# Final.net
KiCad netlist of a schematic drawn in EasyEDA
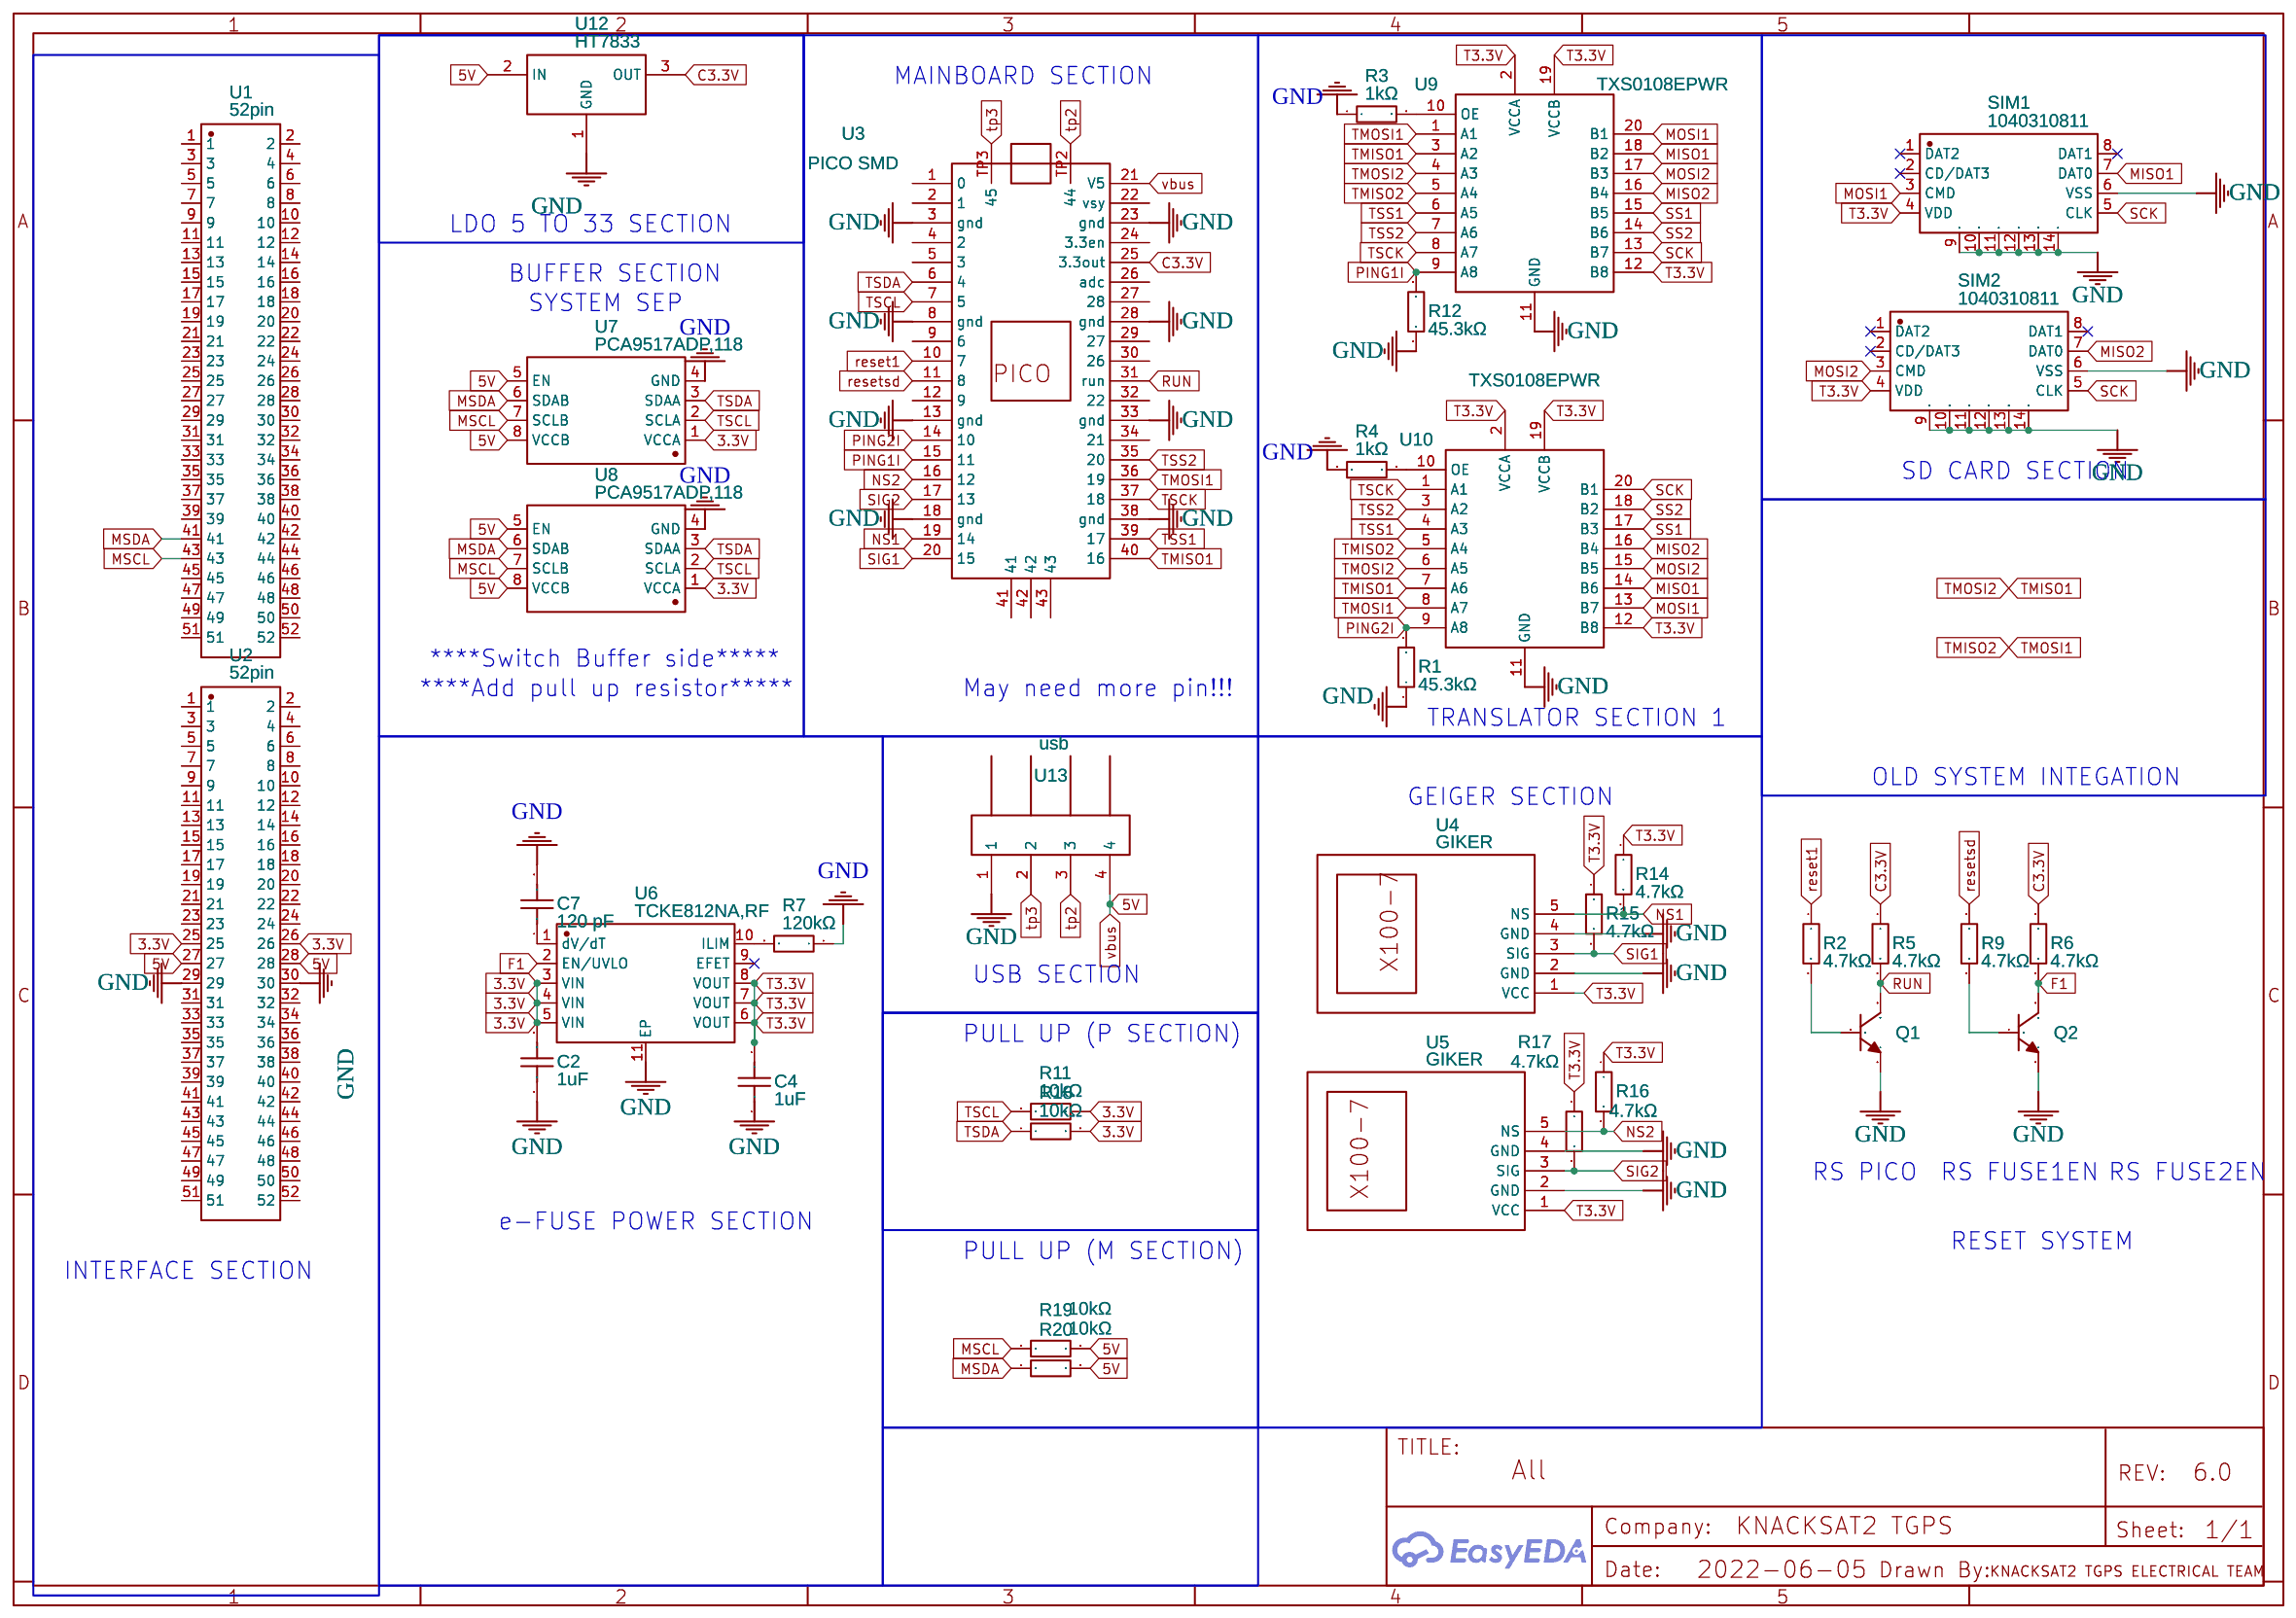
[diagram p0: schematic sheet]

(export (version "E")
  (design (tool "Eeschema 10.0.6"))
  (components
    (comp (ref "C2") (value "1uF") (libsource (lib "") (part "C_0603_US")))
    (comp (ref "C4") (value "1uF") (libsource (lib "") (part "C_0603_US")))
    (comp (ref "C7") (value "120 pF") (libsource (lib "") (part "C_0603_US")))
    (comp (ref "Q1")
      (value "2SC3324-BL(TE85L,F")
      (fields (field (name "BOM_Supplier Part") "C2999171"))
      (libsource (lib "") (part "2SC3324-BL(TE85L,F"))
    )
    (comp (ref "Q2")
      (value "2SC3324-BL(TE85L,F")
      (fields (field (name "BOM_Supplier Part") "C2999171"))
      (libsource (lib "") (part "2SC3324-BL(TE85L,F"))
    )
    (comp (ref "R1")
      (value "45.3kΩ")
      (fields
        (field (name "BOM_Manufacturer Part") "RMC040245.3K1%N")
        (field (name "BOM_Supplier Part") "C325554")
      )
      (libsource (lib "") (part "RMC040245.3K1%N"))
    )
    (comp (ref "R2")
      (value "4.7kΩ")
      (fields
        (field (name "BOM_Manufacturer Part") "RMC08054.7K1%N")
        (field (name "BOM_Supplier Part") "C269746")
      )
      (libsource (lib "") (part "RMC08054.7K1%N"))
    )
    (comp (ref "R3")
      (value "1kΩ")
      (fields
        (field (name "BOM_Manufacturer Part") "PTFR0805B1K00N9")
        (field (name "BOM_Supplier Part") "C328437")
      )
      (libsource (lib "") (part "PTFR0805B1K00N9"))
    )
    (comp (ref "R4")
      (value "1kΩ")
      (fields
        (field (name "BOM_Manufacturer Part") "PTFR0805B1K00N9")
        (field (name "BOM_Supplier Part") "C328437")
      )
      (libsource (lib "") (part "PTFR0805B1K00N9"))
    )
    (comp (ref "R5")
      (value "4.7kΩ")
      (fields
        (field (name "BOM_Manufacturer Part") "RMC08054.7K1%N")
        (field (name "BOM_Supplier Part") "C269746")
      )
      (libsource (lib "") (part "RMC08054.7K1%N"))
    )
    (comp (ref "R6")
      (value "4.7kΩ")
      (fields
        (field (name "BOM_Manufacturer Part") "RMC08054.7K1%N")
        (field (name "BOM_Supplier Part") "C269746")
      )
      (libsource (lib "") (part "RMC08054.7K1%N"))
    )
    (comp (ref "R7")
      (value "120kΩ")
      (fields
        (field (name "BOM_Manufacturer Part") "RMC0402120K1%N")
        (field (name "BOM_Supplier Part") "C325558")
      )
      (libsource (lib "") (part "RMC0402120K1%N"))
    )
    (comp (ref "R9")
      (value "4.7kΩ")
      (fields
        (field (name "BOM_Manufacturer Part") "RMC08054.7K1%N")
        (field (name "BOM_Supplier Part") "C269746")
      )
      (libsource (lib "") (part "RMC08054.7K1%N"))
    )
    (comp (ref "R11")
      (value "10kΩ")
      (fields
        (field (name "BOM_Manufacturer Part") "AECR0805F10K0K9")
        (field (name "BOM_Supplier Part") "C328381")
      )
      (libsource (lib "") (part "AECR0805F10K0K9"))
    )
    (comp (ref "R12")
      (value "45.3kΩ")
      (fields
        (field (name "BOM_Manufacturer Part") "RMC040245.3K1%N")
        (field (name "BOM_Supplier Part") "C325554")
      )
      (libsource (lib "") (part "RMC040245.3K1%N"))
    )
    (comp (ref "R14")
      (value "4.7kΩ")
      (fields
        (field (name "BOM_Manufacturer Part") "RMC08054.7K1%N")
        (field (name "BOM_Supplier Part") "C269746")
      )
      (libsource (lib "") (part "RMC08054.7K1%N"))
    )
    (comp (ref "R15")
      (value "4.7kΩ")
      (fields
        (field (name "BOM_Manufacturer Part") "RMC08054.7K1%N")
        (field (name "BOM_Supplier Part") "C269746")
      )
      (libsource (lib "") (part "RMC08054.7K1%N"))
    )
    (comp (ref "R16")
      (value "4.7kΩ")
      (fields
        (field (name "BOM_Manufacturer Part") "RMC08054.7K1%N")
        (field (name "BOM_Supplier Part") "C269746")
      )
      (libsource (lib "") (part "RMC08054.7K1%N"))
    )
    (comp (ref "R17")
      (value "4.7kΩ")
      (fields
        (field (name "BOM_Manufacturer Part") "RMC08054.7K1%N")
        (field (name "BOM_Supplier Part") "C269746")
      )
      (libsource (lib "") (part "RMC08054.7K1%N"))
    )
    (comp (ref "R18")
      (value "10kΩ")
      (fields
        (field (name "BOM_Manufacturer Part") "AECR0805F10K0K9")
        (field (name "BOM_Supplier Part") "C328381")
      )
      (libsource (lib "") (part "AECR0805F10K0K9"))
    )
    (comp (ref "R19")
      (value "10kΩ")
      (fields
        (field (name "BOM_Manufacturer Part") "AECR0805F10K0K9")
        (field (name "BOM_Supplier Part") "C328381")
      )
      (libsource (lib "") (part "AECR0805F10K0K9"))
    )
    (comp (ref "R20")
      (value "10kΩ")
      (fields
        (field (name "BOM_Manufacturer Part") "AECR0805F10K0K9")
        (field (name "BOM_Supplier Part") "C328381")
      )
      (libsource (lib "") (part "AECR0805F10K0K9"))
    )
    (comp (ref "SIM1")
      (value "1040310811")
      (fields (field (name "BOM_Supplier Part") "C585350"))
      (libsource (lib "") (part "1040310811"))
    )
    (comp (ref "SIM2")
      (value "1040310811")
      (fields (field (name "BOM_Supplier Part") "C585350"))
      (libsource (lib "") (part "1040310811"))
    )
    (comp (ref "U1") (value "52pin") (libsource (lib "") (part "52pin")))
    (comp (ref "U2") (value "52pin") (libsource (lib "") (part "52pin")))
    (comp (ref "U3") (value "PICO SMD") (libsource (lib "") (part "PICO SMD")))
    (comp (ref "U4") (value "GIKER") (libsource (lib "") (part "GIKER")))
    (comp (ref "U5") (value "GIKER") (libsource (lib "") (part "GIKER_1")))
    (comp (ref "U6")
      (value "TCKE812NA,RF")
      (fields (field (name "BOM_Supplier Part") "C1880271"))
      (libsource (lib "") (part "TCKE812NA,RF"))
    )
    (comp (ref "U7")
      (value "PCA9517ADP,118")
      (fields (field (name "BOM_Supplier Part") "C80799"))
      (libsource (lib "") (part "PCA9517ADP,118"))
    )
    (comp (ref "U8")
      (value "PCA9517ADP,118")
      (fields (field (name "BOM_Supplier Part") "C80799"))
      (libsource (lib "") (part "PCA9517ADP,118"))
    )
    (comp (ref "U9")
      (value "TXS0108EPWR")
      (fields (field (name "BOM_Supplier Part") "C17206"))
      (libsource (lib "") (part "TXS0108EPWR"))
    )
    (comp (ref "U10")
      (value "TXS0108EPWR")
      (fields (field (name "BOM_Supplier Part") "C17206"))
      (libsource (lib "") (part "TXS0108EPWR"))
    )
    (comp (ref "U12")
      (value "HT7833")
      (fields (field (name "BOM_Supplier Part") "C50936"))
      (libsource (lib "") (part "HT7833"))
    )
    (comp (ref "U13") (value "usb") (libsource (lib "") (part "usb")))
  )
  (nets
    (net (code "1") (name "3.3V") (class "Default")
      (node (ref "C2") (pin "2") (pinfunction "2_2") (pintype "unspecified"))
      (node (ref "R11") (pin "2") (pinfunction "2_2") (pintype "unspecified"))
      (node (ref "R18") (pin "2") (pinfunction "2_2") (pintype "unspecified"))
      (node (ref "U2") (pin "25") (pinfunction "25_25") (pintype "unspecified"))
      (node (ref "U2") (pin "26") (pinfunction "26_26") (pintype "unspecified"))
      (node (ref "U6") (pin "3") (pinfunction "VIN_3") (pintype "unspecified"))
      (node (ref "U6") (pin "4") (pinfunction "VIN_4") (pintype "unspecified"))
      (node (ref "U6") (pin "5") (pinfunction "VIN_5") (pintype "unspecified"))
      (node (ref "U7") (pin "1") (pinfunction "VCCA_1") (pintype "unspecified"))
      (node (ref "U8") (pin "1") (pinfunction "VCCA_1") (pintype "unspecified"))
    )
    (net (code "2") (name "5V") (class "Default")
      (node (ref "R19") (pin "2") (pinfunction "2_2") (pintype "unspecified"))
      (node (ref "R20") (pin "2") (pinfunction "2_2") (pintype "unspecified"))
      (node (ref "U12") (pin "2") (pinfunction "IN_2") (pintype "passive"))
      (node (ref "U13") (pin "4") (pinfunction "4_4") (pintype "unspecified"))
      (node (ref "U2") (pin "27") (pinfunction "27_27") (pintype "unspecified"))
      (node (ref "U2") (pin "28") (pinfunction "28_28") (pintype "unspecified"))
      (node (ref "U3") (pin "21") (pinfunction "V5_21") (pintype "unspecified"))
      (node (ref "U7") (pin "5") (pinfunction "EN_5") (pintype "unspecified"))
      (node (ref "U7") (pin "8") (pinfunction "VCCB_8") (pintype "unspecified"))
      (node (ref "U8") (pin "5") (pinfunction "EN_5") (pintype "unspecified"))
      (node (ref "U8") (pin "8") (pinfunction "VCCB_8") (pintype "unspecified"))
    )
    (net (code "3") (name "C3.3V") (class "Default")
      (node (ref "R5") (pin "1") (pinfunction "1_1") (pintype "unspecified"))
      (node (ref "R6") (pin "1") (pinfunction "1_1") (pintype "unspecified"))
      (node (ref "U12") (pin "3") (pinfunction "OUT_3") (pintype "passive"))
      (node (ref "U3") (pin "25") (pinfunction "3.3out_25") (pintype "unspecified"))
    )
    (net (code "4") (name "F1") (class "Default")
      (node (ref "Q2") (pin "3") (pinfunction "C_3") (pintype "unspecified"))
      (node (ref "R6") (pin "2") (pinfunction "2_2") (pintype "unspecified"))
      (node (ref "U6") (pin "2") (pinfunction "EN/UVLO_2") (pintype "unspecified"))
    )
    (net (code "5") (name "GND") (class "Default")
      (node (ref "C2") (pin "1") (pinfunction "1_1") (pintype "unspecified"))
      (node (ref "C4") (pin "1") (pinfunction "1_1") (pintype "unspecified"))
      (node (ref "C7") (pin "2") (pinfunction "2_2") (pintype "unspecified"))
      (node (ref "Q1") (pin "2") (pinfunction "E_2") (pintype "unspecified"))
      (node (ref "Q2") (pin "2") (pinfunction "E_2") (pintype "unspecified"))
      (node (ref "R1") (pin "1") (pinfunction "1_1") (pintype "unspecified"))
      (node (ref "R12") (pin "1") (pinfunction "1_1") (pintype "unspecified"))
      (node (ref "R3") (pin "1") (pinfunction "1_1") (pintype "unspecified"))
      (node (ref "R4") (pin "1") (pinfunction "1_1") (pintype "unspecified"))
      (node (ref "R7") (pin "1") (pinfunction "1_1") (pintype "unspecified"))
      (node (ref "SIM1") (pin "10") (pinfunction "10_10") (pintype "unspecified"))
      (node (ref "SIM1") (pin "11") (pinfunction "11_11") (pintype "unspecified"))
      (node (ref "SIM1") (pin "12") (pinfunction "12_12") (pintype "unspecified"))
      (node (ref "SIM1") (pin "13") (pinfunction "13_13") (pintype "unspecified"))
      (node (ref "SIM1") (pin "14") (pinfunction "14_14") (pintype "unspecified"))
      (node (ref "SIM1") (pin "6") (pinfunction "VSS_6") (pintype "unspecified"))
      (node (ref "SIM1") (pin "9") (pinfunction "9_9") (pintype "unspecified"))
      (node (ref "SIM2") (pin "10") (pinfunction "10_10") (pintype "unspecified"))
      (node (ref "SIM2") (pin "11") (pinfunction "11_11") (pintype "unspecified"))
      (node (ref "SIM2") (pin "12") (pinfunction "12_12") (pintype "unspecified"))
      (node (ref "SIM2") (pin "13") (pinfunction "13_13") (pintype "unspecified"))
      (node (ref "SIM2") (pin "14") (pinfunction "14_14") (pintype "unspecified"))
      (node (ref "SIM2") (pin "6") (pinfunction "VSS_6") (pintype "unspecified"))
      (node (ref "SIM2") (pin "9") (pinfunction "9_9") (pintype "unspecified"))
      (node (ref "U10") (pin "11") (pinfunction "GND_11") (pintype "unspecified"))
      (node (ref "U12") (pin "1") (pinfunction "GND_1") (pintype "passive"))
      (node (ref "U13") (pin "1") (pinfunction "1_1") (pintype "unspecified"))
      (node (ref "U2") (pin "29") (pinfunction "29_29") (pintype "unspecified"))
      (node (ref "U2") (pin "30") (pinfunction "30_30") (pintype "unspecified"))
      (node (ref "U3") (pin "13") (pinfunction "gnd_13") (pintype "unspecified"))
      (node (ref "U3") (pin "18") (pinfunction "gnd_18") (pintype "unspecified"))
      (node (ref "U3") (pin "23") (pinfunction "gnd_23") (pintype "unspecified"))
      (node (ref "U3") (pin "28") (pinfunction "gnd_28") (pintype "unspecified"))
      (node (ref "U3") (pin "3") (pinfunction "gnd_3") (pintype "unspecified"))
      (node (ref "U3") (pin "33") (pinfunction "gnd_33") (pintype "unspecified"))
      (node (ref "U3") (pin "38") (pinfunction "gnd_38") (pintype "unspecified"))
      (node (ref "U3") (pin "8") (pinfunction "gnd_8") (pintype "unspecified"))
      (node (ref "U4") (pin "2") (pinfunction "GND_2") (pintype "unspecified"))
      (node (ref "U4") (pin "4") (pinfunction "GND_4") (pintype "unspecified"))
      (node (ref "U5") (pin "2") (pinfunction "GND_2") (pintype "unspecified"))
      (node (ref "U5") (pin "4") (pinfunction "GND_4") (pintype "unspecified"))
      (node (ref "U6") (pin "11") (pinfunction "EP_11") (pintype "unspecified"))
      (node (ref "U7") (pin "4") (pinfunction "GND_4") (pintype "unspecified"))
      (node (ref "U8") (pin "4") (pinfunction "GND_4") (pintype "unspecified"))
      (node (ref "U9") (pin "11") (pinfunction "GND_11") (pintype "unspecified"))
    )
    (net (code "6") (name "MISO1") (class "Default")
      (node (ref "SIM1") (pin "7") (pinfunction "DAT0_7") (pintype "unspecified"))
      (node (ref "U10") (pin "14") (pinfunction "B6_14") (pintype "unspecified"))
      (node (ref "U9") (pin "18") (pinfunction "B2_18") (pintype "unspecified"))
    )
    (net (code "7") (name "MISO2") (class "Default")
      (node (ref "SIM2") (pin "7") (pinfunction "DAT0_7") (pintype "unspecified"))
      (node (ref "U10") (pin "16") (pinfunction "B4_16") (pintype "unspecified"))
      (node (ref "U9") (pin "16") (pinfunction "B4_16") (pintype "unspecified"))
    )
    (net (code "8") (name "MOSI1") (class "Default")
      (node (ref "SIM1") (pin "3") (pinfunction "CMD_3") (pintype "unspecified"))
      (node (ref "U10") (pin "13") (pinfunction "B7_13") (pintype "unspecified"))
      (node (ref "U9") (pin "20") (pinfunction "B1_20") (pintype "unspecified"))
    )
    (net (code "9") (name "MOSI2") (class "Default")
      (node (ref "SIM2") (pin "3") (pinfunction "CMD_3") (pintype "unspecified"))
      (node (ref "U10") (pin "15") (pinfunction "B5_15") (pintype "unspecified"))
      (node (ref "U9") (pin "17") (pinfunction "B3_17") (pintype "unspecified"))
    )
    (net (code "10") (name "MSCL") (class "Default")
      (node (ref "R19") (pin "1") (pinfunction "1_1") (pintype "unspecified"))
      (node (ref "U1") (pin "43") (pinfunction "43_43") (pintype "unspecified"))
      (node (ref "U7") (pin "7") (pinfunction "SCLB_7") (pintype "unspecified"))
      (node (ref "U8") (pin "7") (pinfunction "SCLB_7") (pintype "unspecified"))
    )
    (net (code "11") (name "MSDA") (class "Default")
      (node (ref "R20") (pin "1") (pinfunction "1_1") (pintype "unspecified"))
      (node (ref "U1") (pin "41") (pinfunction "41_41") (pintype "unspecified"))
      (node (ref "U7") (pin "6") (pinfunction "SDAB_6") (pintype "unspecified"))
      (node (ref "U8") (pin "6") (pinfunction "SDAB_6") (pintype "unspecified"))
    )
    (net (code "12") (name "NS1") (class "Default")
      (node (ref "R14") (pin "2") (pinfunction "2_2") (pintype "unspecified"))
      (node (ref "U3") (pin "19") (pinfunction "14_19") (pintype "unspecified"))
      (node (ref "U4") (pin "5") (pinfunction "NS_5") (pintype "unspecified"))
    )
    (net (code "13") (name "NS2") (class "Default")
      (node (ref "R16") (pin "2") (pinfunction "2_2") (pintype "unspecified"))
      (node (ref "U3") (pin "16") (pinfunction "12_16") (pintype "unspecified"))
      (node (ref "U5") (pin "5") (pinfunction "NS_5") (pintype "unspecified"))
    )
    (net (code "14") (name "Net-(Q1-B)") (class "Default")
      (node (ref "Q1") (pin "1") (pinfunction "B_1") (pintype "unspecified"))
      (node (ref "R2") (pin "2") (pinfunction "2_2") (pintype "unspecified"))
    )
    (net (code "15") (name "Net-(Q2-B)") (class "Default")
      (node (ref "Q2") (pin "1") (pinfunction "B_1") (pintype "unspecified"))
      (node (ref "R9") (pin "2") (pinfunction "2_2") (pintype "unspecified"))
    )
    (net (code "16") (name "Net-(U6-ILIM)") (class "Default")
      (node (ref "R7") (pin "2") (pinfunction "2_2") (pintype "unspecified"))
      (node (ref "U6") (pin "10") (pinfunction "ILIM_10") (pintype "unspecified"))
    )
    (net (code "17") (name "Net-(U6-dV{slash}dT)") (class "Default")
      (node (ref "C7") (pin "1") (pinfunction "1_1") (pintype "unspecified"))
      (node (ref "U6") (pin "1") (pinfunction "dV/dT_1") (pintype "unspecified"))
    )
    (net (code "18") (name "Net-(U9-OE)") (class "Default")
      (node (ref "R3") (pin "2") (pinfunction "2_2") (pintype "unspecified"))
      (node (ref "U9") (pin "10") (pinfunction "OE_10") (pintype "unspecified"))
    )
    (net (code "19") (name "Net-(U10-OE)") (class "Default")
      (node (ref "R4") (pin "2") (pinfunction "2_2") (pintype "unspecified"))
      (node (ref "U10") (pin "10") (pinfunction "OE_10") (pintype "unspecified"))
    )
    (net (code "20") (name "PING1I") (class "Default")
      (node (ref "R12") (pin "2") (pinfunction "2_2") (pintype "unspecified"))
      (node (ref "U3") (pin "15") (pinfunction "11_15") (pintype "unspecified"))
      (node (ref "U9") (pin "9") (pinfunction "A8_9") (pintype "unspecified"))
    )
    (net (code "21") (name "PING2I") (class "Default")
      (node (ref "R1") (pin "2") (pinfunction "2_2") (pintype "unspecified"))
      (node (ref "U10") (pin "9") (pinfunction "A8_9") (pintype "unspecified"))
      (node (ref "U3") (pin "14") (pinfunction "10_14") (pintype "unspecified"))
    )
    (net (code "22") (name "RUN") (class "Default")
      (node (ref "Q1") (pin "3") (pinfunction "C_3") (pintype "unspecified"))
      (node (ref "R5") (pin "2") (pinfunction "2_2") (pintype "unspecified"))
      (node (ref "U3") (pin "31") (pinfunction "run_31") (pintype "unspecified"))
    )
    (net (code "23") (name "SCK") (class "Default")
      (node (ref "SIM1") (pin "5") (pinfunction "CLK_5") (pintype "unspecified"))
      (node (ref "SIM2") (pin "5") (pinfunction "CLK_5") (pintype "unspecified"))
      (node (ref "U10") (pin "20") (pinfunction "B1_20") (pintype "unspecified"))
      (node (ref "U9") (pin "13") (pinfunction "B7_13") (pintype "unspecified"))
    )
    (net (code "24") (name "SIG1") (class "Default")
      (node (ref "R15") (pin "2") (pinfunction "2_2") (pintype "unspecified"))
      (node (ref "U3") (pin "20") (pinfunction "15_20") (pintype "unspecified"))
      (node (ref "U4") (pin "3") (pinfunction "SIG_3") (pintype "unspecified"))
    )
    (net (code "25") (name "SIG2") (class "Default")
      (node (ref "R17") (pin "2") (pinfunction "2_2") (pintype "unspecified"))
      (node (ref "U3") (pin "17") (pinfunction "13_17") (pintype "unspecified"))
      (node (ref "U5") (pin "3") (pinfunction "SIG_3") (pintype "unspecified"))
    )
    (net (code "26") (name "SS1") (class "Default")
      (node (ref "U10") (pin "17") (pinfunction "B3_17") (pintype "unspecified"))
      (node (ref "U9") (pin "15") (pinfunction "B5_15") (pintype "unspecified"))
    )
    (net (code "27") (name "SS2") (class "Default")
      (node (ref "U10") (pin "18") (pinfunction "B2_18") (pintype "unspecified"))
      (node (ref "U9") (pin "14") (pinfunction "B6_14") (pintype "unspecified"))
    )
    (net (code "28") (name "T3.3V") (class "Default")
      (node (ref "C4") (pin "2") (pinfunction "2_2") (pintype "unspecified"))
      (node (ref "R14") (pin "1") (pinfunction "1_1") (pintype "unspecified"))
      (node (ref "R15") (pin "1") (pinfunction "1_1") (pintype "unspecified"))
      (node (ref "R16") (pin "1") (pinfunction "1_1") (pintype "unspecified"))
      (node (ref "R17") (pin "1") (pinfunction "1_1") (pintype "unspecified"))
      (node (ref "SIM1") (pin "4") (pinfunction "VDD_4") (pintype "unspecified"))
      (node (ref "SIM2") (pin "4") (pinfunction "VDD_4") (pintype "unspecified"))
      (node (ref "U10") (pin "12") (pinfunction "B8_12") (pintype "unspecified"))
      (node (ref "U10") (pin "19") (pinfunction "VCCB_19") (pintype "unspecified"))
      (node (ref "U10") (pin "2") (pinfunction "VCCA_2") (pintype "unspecified"))
      (node (ref "U4") (pin "1") (pinfunction "VCC_1") (pintype "unspecified"))
      (node (ref "U5") (pin "1") (pinfunction "VCC_1") (pintype "unspecified"))
      (node (ref "U6") (pin "6") (pinfunction "VOUT_6") (pintype "unspecified"))
      (node (ref "U6") (pin "7") (pinfunction "VOUT_7") (pintype "unspecified"))
      (node (ref "U6") (pin "8") (pinfunction "VOUT_8") (pintype "unspecified"))
      (node (ref "U9") (pin "12") (pinfunction "B8_12") (pintype "unspecified"))
      (node (ref "U9") (pin "19") (pinfunction "VCCB_19") (pintype "unspecified"))
      (node (ref "U9") (pin "2") (pinfunction "VCCA_2") (pintype "unspecified"))
    )
    (net (code "29") (name "TMISO1") (class "Default")
      (node (ref "U10") (pin "6") (pinfunction "A5_6") (pintype "unspecified"))
      (node (ref "U10") (pin "7") (pinfunction "A6_7") (pintype "unspecified"))
      (node (ref "U3") (pin "40") (pinfunction "16_40") (pintype "unspecified"))
      (node (ref "U9") (pin "3") (pinfunction "A2_3") (pintype "unspecified"))
      (node (ref "U9") (pin "4") (pinfunction "A3_4") (pintype "unspecified"))
    )
    (net (code "30") (name "TMISO2") (class "Default")
      (node (ref "U10") (pin "5") (pinfunction "A4_5") (pintype "unspecified"))
      (node (ref "U10") (pin "8") (pinfunction "A7_8") (pintype "unspecified"))
      (node (ref "U3") (pin "36") (pinfunction "19_36") (pintype "unspecified"))
      (node (ref "U9") (pin "1") (pinfunction "A1_1") (pintype "unspecified"))
      (node (ref "U9") (pin "5") (pinfunction "A4_5") (pintype "unspecified"))
    )
    (net (code "31") (name "TSCK") (class "Default")
      (node (ref "U10") (pin "1") (pinfunction "A1_1") (pintype "unspecified"))
      (node (ref "U3") (pin "37") (pinfunction "18_37") (pintype "unspecified"))
      (node (ref "U9") (pin "8") (pinfunction "A7_8") (pintype "unspecified"))
    )
    (net (code "32") (name "TSCL") (class "Default")
      (node (ref "R11") (pin "1") (pinfunction "1_1") (pintype "unspecified"))
      (node (ref "U3") (pin "7") (pinfunction "5_7") (pintype "unspecified"))
      (node (ref "U7") (pin "2") (pinfunction "SCLA_2") (pintype "unspecified"))
      (node (ref "U8") (pin "2") (pinfunction "SCLA_2") (pintype "unspecified"))
    )
    (net (code "33") (name "TSDA") (class "Default")
      (node (ref "R18") (pin "1") (pinfunction "1_1") (pintype "unspecified"))
      (node (ref "U3") (pin "6") (pinfunction "4_6") (pintype "unspecified"))
      (node (ref "U7") (pin "3") (pinfunction "SDAA_3") (pintype "unspecified"))
      (node (ref "U8") (pin "3") (pinfunction "SDAA_3") (pintype "unspecified"))
    )
    (net (code "34") (name "TSS1") (class "Default")
      (node (ref "U10") (pin "4") (pinfunction "A3_4") (pintype "unspecified"))
      (node (ref "U3") (pin "39") (pinfunction "17_39") (pintype "unspecified"))
      (node (ref "U9") (pin "6") (pinfunction "A5_6") (pintype "unspecified"))
    )
    (net (code "35") (name "TSS2") (class "Default")
      (node (ref "U10") (pin "3") (pinfunction "A2_3") (pintype "unspecified"))
      (node (ref "U3") (pin "35") (pinfunction "20_35") (pintype "unspecified"))
      (node (ref "U9") (pin "7") (pinfunction "A6_7") (pintype "unspecified"))
    )
    (net (code "36") (name "reset1") (class "Default")
      (node (ref "R2") (pin "1") (pinfunction "1_1") (pintype "unspecified"))
      (node (ref "U3") (pin "10") (pinfunction "7_10") (pintype "unspecified"))
    )
    (net (code "37") (name "resetsd") (class "Default")
      (node (ref "R9") (pin "1") (pinfunction "1_1") (pintype "unspecified"))
      (node (ref "U3") (pin "11") (pinfunction "8_11") (pintype "unspecified"))
    )
    (net (code "38") (name "tp2") (class "Default")
      (node (ref "U13") (pin "3") (pinfunction "3_3") (pintype "unspecified"))
      (node (ref "U3") (pin "TP2") (pinfunction "44_TP2") (pintype "unspecified"))
    )
    (net (code "39") (name "tp3") (class "Default")
      (node (ref "U13") (pin "2") (pinfunction "2_2") (pintype "unspecified"))
      (node (ref "U3") (pin "TP3") (pinfunction "45_TP3") (pintype "unspecified"))
    )
    (net (code "40") (name "unconnected-(SIM1-CD{slash}DAT3-Pad2)") (class "Default")
      (node (ref "SIM1") (pin "2") (pinfunction "CD/DAT3_2") (pintype "unspecified+no_connect"))
    )
    (net (code "41") (name "unconnected-(SIM1-DAT1-Pad8)") (class "Default")
      (node (ref "SIM1") (pin "8") (pinfunction "DAT1_8") (pintype "unspecified+no_connect"))
    )
    (net (code "42") (name "unconnected-(SIM1-DAT2-Pad1)") (class "Default")
      (node (ref "SIM1") (pin "1") (pinfunction "DAT2_1") (pintype "unspecified+no_connect"))
    )
    (net (code "43") (name "unconnected-(SIM2-CD{slash}DAT3-Pad2)") (class "Default")
      (node (ref "SIM2") (pin "2") (pinfunction "CD/DAT3_2") (pintype "unspecified+no_connect"))
    )
    (net (code "44") (name "unconnected-(SIM2-DAT1-Pad8)") (class "Default")
      (node (ref "SIM2") (pin "8") (pinfunction "DAT1_8") (pintype "unspecified+no_connect"))
    )
    (net (code "45") (name "unconnected-(SIM2-DAT2-Pad1)") (class "Default")
      (node (ref "SIM2") (pin "1") (pinfunction "DAT2_1") (pintype "unspecified+no_connect"))
    )
    (net (code "46") (name "unconnected-(U1-Pad1)") (class "Default")
      (node (ref "U1") (pin "1") (pinfunction "1_1") (pintype "unspecified"))
    )
    (net (code "47") (name "unconnected-(U1-Pad2)") (class "Default")
      (node (ref "U1") (pin "2") (pinfunction "2_2") (pintype "unspecified"))
    )
    (net (code "48") (name "unconnected-(U1-Pad3)") (class "Default")
      (node (ref "U1") (pin "3") (pinfunction "3_3") (pintype "unspecified"))
    )
    (net (code "49") (name "unconnected-(U1-Pad4)") (class "Default")
      (node (ref "U1") (pin "4") (pinfunction "4_4") (pintype "unspecified"))
    )
    (net (code "50") (name "unconnected-(U1-Pad5)") (class "Default")
      (node (ref "U1") (pin "5") (pinfunction "5_5") (pintype "unspecified"))
    )
    (net (code "51") (name "unconnected-(U1-Pad6)") (class "Default")
      (node (ref "U1") (pin "6") (pinfunction "6_6") (pintype "unspecified"))
    )
    (net (code "52") (name "unconnected-(U1-Pad7)") (class "Default")
      (node (ref "U1") (pin "7") (pinfunction "7_7") (pintype "unspecified"))
    )
    (net (code "53") (name "unconnected-(U1-Pad8)") (class "Default")
      (node (ref "U1") (pin "8") (pinfunction "8_8") (pintype "unspecified"))
    )
    (net (code "54") (name "unconnected-(U1-Pad9)") (class "Default")
      (node (ref "U1") (pin "9") (pinfunction "9_9") (pintype "unspecified"))
    )
    (net (code "55") (name "unconnected-(U1-Pad10)") (class "Default")
      (node (ref "U1") (pin "10") (pinfunction "10_10") (pintype "unspecified"))
    )
    (net (code "56") (name "unconnected-(U1-Pad11)") (class "Default")
      (node (ref "U1") (pin "11") (pinfunction "11_11") (pintype "unspecified"))
    )
    (net (code "57") (name "unconnected-(U1-Pad12)") (class "Default")
      (node (ref "U1") (pin "12") (pinfunction "12_12") (pintype "unspecified"))
    )
    (net (code "58") (name "unconnected-(U1-Pad13)") (class "Default")
      (node (ref "U1") (pin "13") (pinfunction "13_13") (pintype "unspecified"))
    )
    (net (code "59") (name "unconnected-(U1-Pad14)") (class "Default")
      (node (ref "U1") (pin "14") (pinfunction "14_14") (pintype "unspecified"))
    )
    (net (code "60") (name "unconnected-(U1-Pad15)") (class "Default")
      (node (ref "U1") (pin "15") (pinfunction "15_15") (pintype "unspecified"))
    )
    (net (code "61") (name "unconnected-(U1-Pad16)") (class "Default")
      (node (ref "U1") (pin "16") (pinfunction "16_16") (pintype "unspecified"))
    )
    (net (code "62") (name "unconnected-(U1-Pad17)") (class "Default")
      (node (ref "U1") (pin "17") (pinfunction "17_17") (pintype "unspecified"))
    )
    (net (code "63") (name "unconnected-(U1-Pad18)") (class "Default")
      (node (ref "U1") (pin "18") (pinfunction "18_18") (pintype "unspecified"))
    )
    (net (code "64") (name "unconnected-(U1-Pad19)") (class "Default")
      (node (ref "U1") (pin "19") (pinfunction "19_19") (pintype "unspecified"))
    )
    (net (code "65") (name "unconnected-(U1-Pad20)") (class "Default")
      (node (ref "U1") (pin "20") (pinfunction "20_20") (pintype "unspecified"))
    )
    (net (code "66") (name "unconnected-(U1-Pad21)") (class "Default")
      (node (ref "U1") (pin "21") (pinfunction "21_21") (pintype "unspecified"))
    )
    (net (code "67") (name "unconnected-(U1-Pad22)") (class "Default")
      (node (ref "U1") (pin "22") (pinfunction "22_22") (pintype "unspecified"))
    )
    (net (code "68") (name "unconnected-(U1-Pad23)") (class "Default")
      (node (ref "U1") (pin "23") (pinfunction "23_23") (pintype "unspecified"))
    )
    (net (code "69") (name "unconnected-(U1-Pad24)") (class "Default")
      (node (ref "U1") (pin "24") (pinfunction "24_24") (pintype "unspecified"))
    )
    (net (code "70") (name "unconnected-(U1-Pad25)") (class "Default")
      (node (ref "U1") (pin "25") (pinfunction "25_25") (pintype "unspecified"))
    )
    (net (code "71") (name "unconnected-(U1-Pad26)") (class "Default")
      (node (ref "U1") (pin "26") (pinfunction "26_26") (pintype "unspecified"))
    )
    (net (code "72") (name "unconnected-(U1-Pad27)") (class "Default")
      (node (ref "U1") (pin "27") (pinfunction "27_27") (pintype "unspecified"))
    )
    (net (code "73") (name "unconnected-(U1-Pad28)") (class "Default")
      (node (ref "U1") (pin "28") (pinfunction "28_28") (pintype "unspecified"))
    )
    (net (code "74") (name "unconnected-(U1-Pad29)") (class "Default")
      (node (ref "U1") (pin "29") (pinfunction "29_29") (pintype "unspecified"))
    )
    (net (code "75") (name "unconnected-(U1-Pad30)") (class "Default")
      (node (ref "U1") (pin "30") (pinfunction "30_30") (pintype "unspecified"))
    )
    (net (code "76") (name "unconnected-(U1-Pad31)") (class "Default")
      (node (ref "U1") (pin "31") (pinfunction "31_31") (pintype "unspecified"))
    )
    (net (code "77") (name "unconnected-(U1-Pad32)") (class "Default")
      (node (ref "U1") (pin "32") (pinfunction "32_32") (pintype "unspecified"))
    )
    (net (code "78") (name "unconnected-(U1-Pad33)") (class "Default")
      (node (ref "U1") (pin "33") (pinfunction "33_33") (pintype "unspecified"))
    )
    (net (code "79") (name "unconnected-(U1-Pad34)") (class "Default")
      (node (ref "U1") (pin "34") (pinfunction "34_34") (pintype "unspecified"))
    )
    (net (code "80") (name "unconnected-(U1-Pad35)") (class "Default")
      (node (ref "U1") (pin "35") (pinfunction "35_35") (pintype "unspecified"))
    )
    (net (code "81") (name "unconnected-(U1-Pad36)") (class "Default")
      (node (ref "U1") (pin "36") (pinfunction "36_36") (pintype "unspecified"))
    )
    (net (code "82") (name "unconnected-(U1-Pad37)") (class "Default")
      (node (ref "U1") (pin "37") (pinfunction "37_37") (pintype "unspecified"))
    )
    (net (code "83") (name "unconnected-(U1-Pad38)") (class "Default")
      (node (ref "U1") (pin "38") (pinfunction "38_38") (pintype "unspecified"))
    )
    (net (code "84") (name "unconnected-(U1-Pad39)") (class "Default")
      (node (ref "U1") (pin "39") (pinfunction "39_39") (pintype "unspecified"))
    )
    (net (code "85") (name "unconnected-(U1-Pad40)") (class "Default")
      (node (ref "U1") (pin "40") (pinfunction "40_40") (pintype "unspecified"))
    )
    (net (code "86") (name "unconnected-(U1-Pad42)") (class "Default")
      (node (ref "U1") (pin "42") (pinfunction "42_42") (pintype "unspecified"))
    )
    (net (code "87") (name "unconnected-(U1-Pad44)") (class "Default")
      (node (ref "U1") (pin "44") (pinfunction "44_44") (pintype "unspecified"))
    )
    (net (code "88") (name "unconnected-(U1-Pad45)") (class "Default")
      (node (ref "U1") (pin "45") (pinfunction "45_45") (pintype "unspecified"))
    )
    (net (code "89") (name "unconnected-(U1-Pad46)") (class "Default")
      (node (ref "U1") (pin "46") (pinfunction "46_46") (pintype "unspecified"))
    )
    (net (code "90") (name "unconnected-(U1-Pad47)") (class "Default")
      (node (ref "U1") (pin "47") (pinfunction "47_47") (pintype "unspecified"))
    )
    (net (code "91") (name "unconnected-(U1-Pad48)") (class "Default")
      (node (ref "U1") (pin "48") (pinfunction "48_48") (pintype "unspecified"))
    )
    (net (code "92") (name "unconnected-(U1-Pad49)") (class "Default")
      (node (ref "U1") (pin "49") (pinfunction "49_49") (pintype "unspecified"))
    )
    (net (code "93") (name "unconnected-(U1-Pad50)") (class "Default")
      (node (ref "U1") (pin "50") (pinfunction "50_50") (pintype "unspecified"))
    )
    (net (code "94") (name "unconnected-(U1-Pad51)") (class "Default")
      (node (ref "U1") (pin "51") (pinfunction "51_51") (pintype "unspecified"))
    )
    (net (code "95") (name "unconnected-(U1-Pad52)") (class "Default")
      (node (ref "U1") (pin "52") (pinfunction "52_52") (pintype "unspecified"))
    )
    (net (code "96") (name "unconnected-(U2-Pad1)") (class "Default")
      (node (ref "U2") (pin "1") (pinfunction "1_1") (pintype "unspecified"))
    )
    (net (code "97") (name "unconnected-(U2-Pad2)") (class "Default")
      (node (ref "U2") (pin "2") (pinfunction "2_2") (pintype "unspecified"))
    )
    (net (code "98") (name "unconnected-(U2-Pad3)") (class "Default")
      (node (ref "U2") (pin "3") (pinfunction "3_3") (pintype "unspecified"))
    )
    (net (code "99") (name "unconnected-(U2-Pad4)") (class "Default")
      (node (ref "U2") (pin "4") (pinfunction "4_4") (pintype "unspecified"))
    )
    (net (code "100") (name "unconnected-(U2-Pad5)") (class "Default")
      (node (ref "U2") (pin "5") (pinfunction "5_5") (pintype "unspecified"))
    )
    (net (code "101") (name "unconnected-(U2-Pad6)") (class "Default")
      (node (ref "U2") (pin "6") (pinfunction "6_6") (pintype "unspecified"))
    )
    (net (code "102") (name "unconnected-(U2-Pad7)") (class "Default")
      (node (ref "U2") (pin "7") (pinfunction "7_7") (pintype "unspecified"))
    )
    (net (code "103") (name "unconnected-(U2-Pad8)") (class "Default")
      (node (ref "U2") (pin "8") (pinfunction "8_8") (pintype "unspecified"))
    )
    (net (code "104") (name "unconnected-(U2-Pad9)") (class "Default")
      (node (ref "U2") (pin "9") (pinfunction "9_9") (pintype "unspecified"))
    )
    (net (code "105") (name "unconnected-(U2-Pad10)") (class "Default")
      (node (ref "U2") (pin "10") (pinfunction "10_10") (pintype "unspecified"))
    )
    (net (code "106") (name "unconnected-(U2-Pad11)") (class "Default")
      (node (ref "U2") (pin "11") (pinfunction "11_11") (pintype "unspecified"))
    )
    (net (code "107") (name "unconnected-(U2-Pad12)") (class "Default")
      (node (ref "U2") (pin "12") (pinfunction "12_12") (pintype "unspecified"))
    )
    (net (code "108") (name "unconnected-(U2-Pad13)") (class "Default")
      (node (ref "U2") (pin "13") (pinfunction "13_13") (pintype "unspecified"))
    )
    (net (code "109") (name "unconnected-(U2-Pad14)") (class "Default")
      (node (ref "U2") (pin "14") (pinfunction "14_14") (pintype "unspecified"))
    )
    (net (code "110") (name "unconnected-(U2-Pad15)") (class "Default")
      (node (ref "U2") (pin "15") (pinfunction "15_15") (pintype "unspecified"))
    )
    (net (code "111") (name "unconnected-(U2-Pad16)") (class "Default")
      (node (ref "U2") (pin "16") (pinfunction "16_16") (pintype "unspecified"))
    )
    (net (code "112") (name "unconnected-(U2-Pad17)") (class "Default")
      (node (ref "U2") (pin "17") (pinfunction "17_17") (pintype "unspecified"))
    )
    (net (code "113") (name "unconnected-(U2-Pad18)") (class "Default")
      (node (ref "U2") (pin "18") (pinfunction "18_18") (pintype "unspecified"))
    )
    (net (code "114") (name "unconnected-(U2-Pad19)") (class "Default")
      (node (ref "U2") (pin "19") (pinfunction "19_19") (pintype "unspecified"))
    )
    (net (code "115") (name "unconnected-(U2-Pad20)") (class "Default")
      (node (ref "U2") (pin "20") (pinfunction "20_20") (pintype "unspecified"))
    )
    (net (code "116") (name "unconnected-(U2-Pad21)") (class "Default")
      (node (ref "U2") (pin "21") (pinfunction "21_21") (pintype "unspecified"))
    )
    (net (code "117") (name "unconnected-(U2-Pad22)") (class "Default")
      (node (ref "U2") (pin "22") (pinfunction "22_22") (pintype "unspecified"))
    )
    (net (code "118") (name "unconnected-(U2-Pad23)") (class "Default")
      (node (ref "U2") (pin "23") (pinfunction "23_23") (pintype "unspecified"))
    )
    (net (code "119") (name "unconnected-(U2-Pad24)") (class "Default")
      (node (ref "U2") (pin "24") (pinfunction "24_24") (pintype "unspecified"))
    )
    (net (code "120") (name "unconnected-(U2-Pad31)") (class "Default")
      (node (ref "U2") (pin "31") (pinfunction "31_31") (pintype "unspecified"))
    )
    (net (code "121") (name "unconnected-(U2-Pad32)") (class "Default")
      (node (ref "U2") (pin "32") (pinfunction "32_32") (pintype "unspecified"))
    )
    (net (code "122") (name "unconnected-(U2-Pad33)") (class "Default")
      (node (ref "U2") (pin "33") (pinfunction "33_33") (pintype "unspecified"))
    )
    (net (code "123") (name "unconnected-(U2-Pad34)") (class "Default")
      (node (ref "U2") (pin "34") (pinfunction "34_34") (pintype "unspecified"))
    )
    (net (code "124") (name "unconnected-(U2-Pad35)") (class "Default")
      (node (ref "U2") (pin "35") (pinfunction "35_35") (pintype "unspecified"))
    )
    (net (code "125") (name "unconnected-(U2-Pad36)") (class "Default")
      (node (ref "U2") (pin "36") (pinfunction "36_36") (pintype "unspecified"))
    )
    (net (code "126") (name "unconnected-(U2-Pad37)") (class "Default")
      (node (ref "U2") (pin "37") (pinfunction "37_37") (pintype "unspecified"))
    )
    (net (code "127") (name "unconnected-(U2-Pad38)") (class "Default")
      (node (ref "U2") (pin "38") (pinfunction "38_38") (pintype "unspecified"))
    )
    (net (code "128") (name "unconnected-(U2-Pad39)") (class "Default")
      (node (ref "U2") (pin "39") (pinfunction "39_39") (pintype "unspecified"))
    )
    (net (code "129") (name "unconnected-(U2-Pad40)") (class "Default")
      (node (ref "U2") (pin "40") (pinfunction "40_40") (pintype "unspecified"))
    )
    (net (code "130") (name "unconnected-(U2-Pad41)") (class "Default")
      (node (ref "U2") (pin "41") (pinfunction "41_41") (pintype "unspecified"))
    )
    (net (code "131") (name "unconnected-(U2-Pad42)") (class "Default")
      (node (ref "U2") (pin "42") (pinfunction "42_42") (pintype "unspecified"))
    )
    (net (code "132") (name "unconnected-(U2-Pad43)") (class "Default")
      (node (ref "U2") (pin "43") (pinfunction "43_43") (pintype "unspecified"))
    )
    (net (code "133") (name "unconnected-(U2-Pad44)") (class "Default")
      (node (ref "U2") (pin "44") (pinfunction "44_44") (pintype "unspecified"))
    )
    (net (code "134") (name "unconnected-(U2-Pad45)") (class "Default")
      (node (ref "U2") (pin "45") (pinfunction "45_45") (pintype "unspecified"))
    )
    (net (code "135") (name "unconnected-(U2-Pad46)") (class "Default")
      (node (ref "U2") (pin "46") (pinfunction "46_46") (pintype "unspecified"))
    )
    (net (code "136") (name "unconnected-(U2-Pad47)") (class "Default")
      (node (ref "U2") (pin "47") (pinfunction "47_47") (pintype "unspecified"))
    )
    (net (code "137") (name "unconnected-(U2-Pad48)") (class "Default")
      (node (ref "U2") (pin "48") (pinfunction "48_48") (pintype "unspecified"))
    )
    (net (code "138") (name "unconnected-(U2-Pad49)") (class "Default")
      (node (ref "U2") (pin "49") (pinfunction "49_49") (pintype "unspecified"))
    )
    (net (code "139") (name "unconnected-(U2-Pad50)") (class "Default")
      (node (ref "U2") (pin "50") (pinfunction "50_50") (pintype "unspecified"))
    )
    (net (code "140") (name "unconnected-(U2-Pad51)") (class "Default")
      (node (ref "U2") (pin "51") (pinfunction "51_51") (pintype "unspecified"))
    )
    (net (code "141") (name "unconnected-(U2-Pad52)") (class "Default")
      (node (ref "U2") (pin "52") (pinfunction "52_52") (pintype "unspecified"))
    )
    (net (code "142") (name "unconnected-(U3-0-Pad1)") (class "Default")
      (node (ref "U3") (pin "1") (pinfunction "0_1") (pintype "unspecified"))
    )
    (net (code "143") (name "unconnected-(U3-1-Pad2)") (class "Default")
      (node (ref "U3") (pin "2") (pinfunction "1_2") (pintype "unspecified"))
    )
    (net (code "144") (name "unconnected-(U3-2-Pad4)") (class "Default")
      (node (ref "U3") (pin "4") (pinfunction "2_4") (pintype "unspecified"))
    )
    (net (code "145") (name "unconnected-(U3-3-Pad5)") (class "Default")
      (node (ref "U3") (pin "5") (pinfunction "3_5") (pintype "unspecified"))
    )
    (net (code "146") (name "unconnected-(U3-3.3en-Pad24)") (class "Default")
      (node (ref "U3") (pin "24") (pinfunction "3.3en_24") (pintype "unspecified"))
    )
    (net (code "147") (name "unconnected-(U3-6-Pad9)") (class "Default")
      (node (ref "U3") (pin "9") (pinfunction "6_9") (pintype "unspecified"))
    )
    (net (code "148") (name "unconnected-(U3-9-Pad12)") (class "Default")
      (node (ref "U3") (pin "12") (pinfunction "9_12") (pintype "unspecified"))
    )
    (net (code "149") (name "unconnected-(U3-21-Pad34)") (class "Default")
      (node (ref "U3") (pin "34") (pinfunction "21_34") (pintype "unspecified"))
    )
    (net (code "150") (name "unconnected-(U3-22-Pad32)") (class "Default")
      (node (ref "U3") (pin "32") (pinfunction "22_32") (pintype "unspecified"))
    )
    (net (code "151") (name "unconnected-(U3-26-Pad30)") (class "Default")
      (node (ref "U3") (pin "30") (pinfunction "26_30") (pintype "unspecified"))
    )
    (net (code "152") (name "unconnected-(U3-27-Pad29)") (class "Default")
      (node (ref "U3") (pin "29") (pinfunction "27_29") (pintype "unspecified"))
    )
    (net (code "153") (name "unconnected-(U3-28-Pad27)") (class "Default")
      (node (ref "U3") (pin "27") (pinfunction "28_27") (pintype "unspecified"))
    )
    (net (code "154") (name "unconnected-(U3-Pad41)") (class "Default")
      (node (ref "U3") (pin "41") (pinfunction "41_41") (pintype "unspecified"))
    )
    (net (code "155") (name "unconnected-(U3-Pad42)") (class "Default")
      (node (ref "U3") (pin "42") (pinfunction "42_42") (pintype "unspecified"))
    )
    (net (code "156") (name "unconnected-(U3-Pad43)") (class "Default")
      (node (ref "U3") (pin "43") (pinfunction "43_43") (pintype "unspecified"))
    )
    (net (code "157") (name "unconnected-(U3-adc-Pad26)") (class "Default")
      (node (ref "U3") (pin "26") (pinfunction "adc_26") (pintype "unspecified"))
    )
    (net (code "158") (name "unconnected-(U3-vsy-Pad22)") (class "Default")
      (node (ref "U3") (pin "22") (pinfunction "vsy_22") (pintype "unspecified"))
    )
    (net (code "159") (name "unconnected-(U6-EFET-Pad9)") (class "Default")
      (node (ref "U6") (pin "9") (pinfunction "EFET_9") (pintype "unspecified+no_connect"))
    )
  )
)
